# dataloggerver4_1.net
KiCad netlist of a schematic drawn in EAGLE
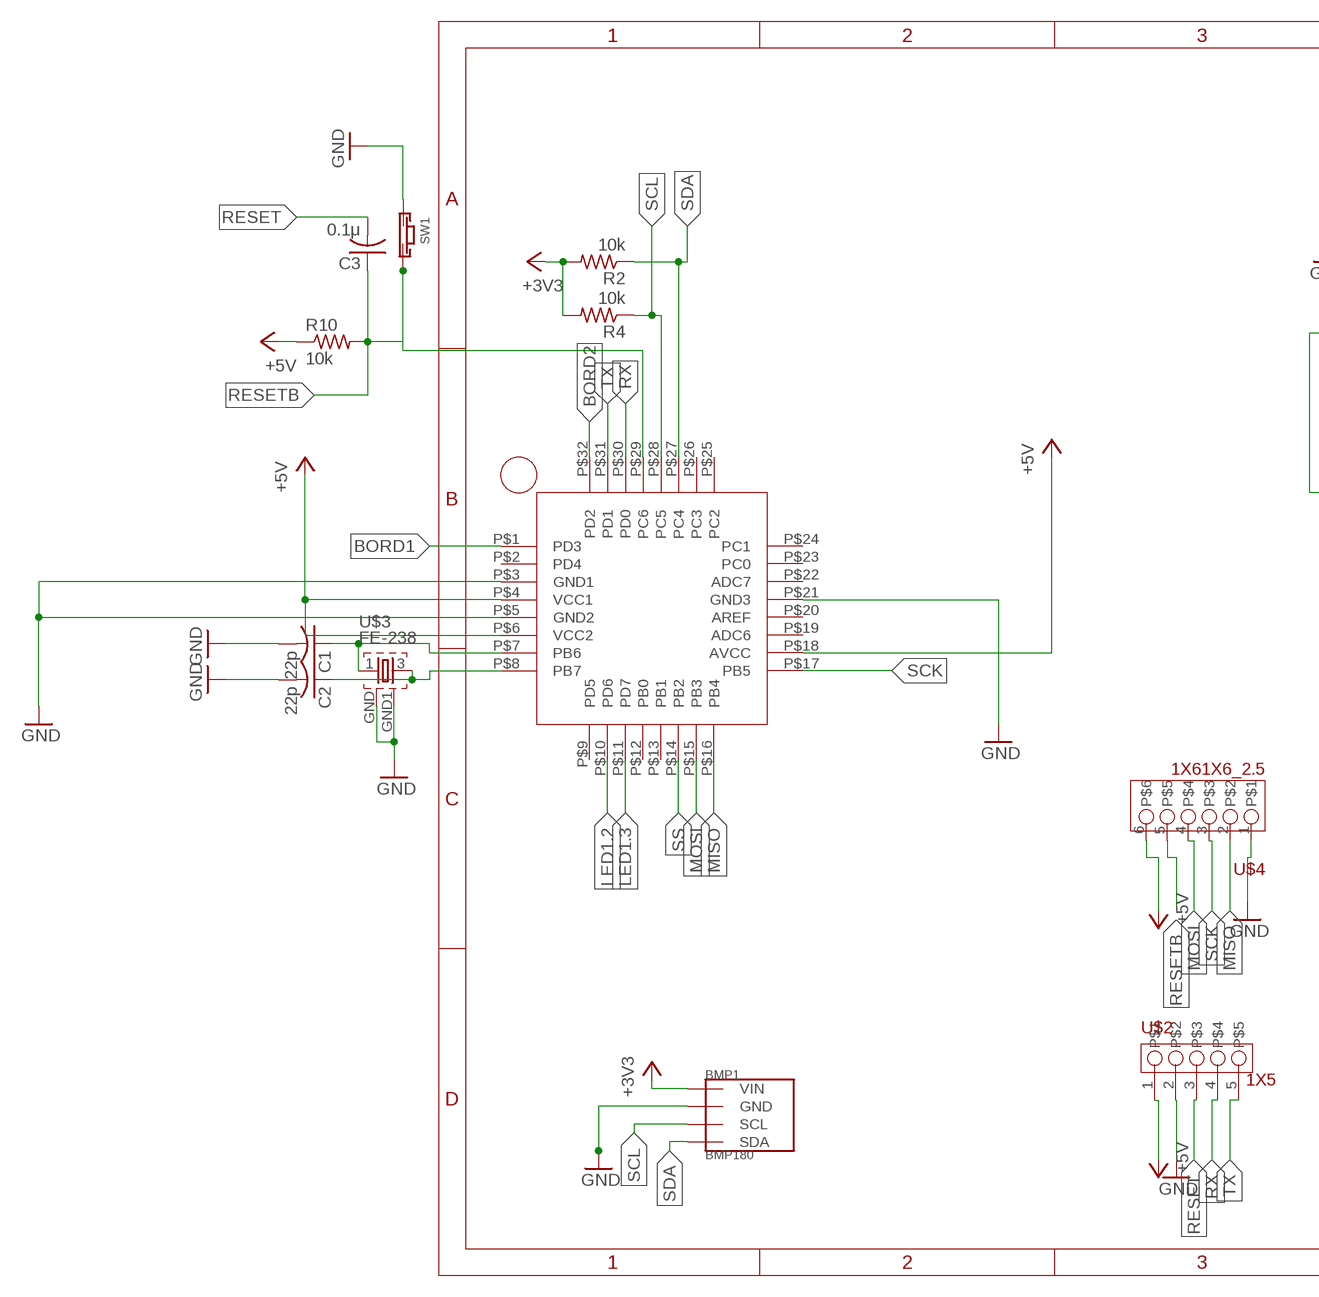
[diagram p0: schematic, sheet 1, part 1 of 2]
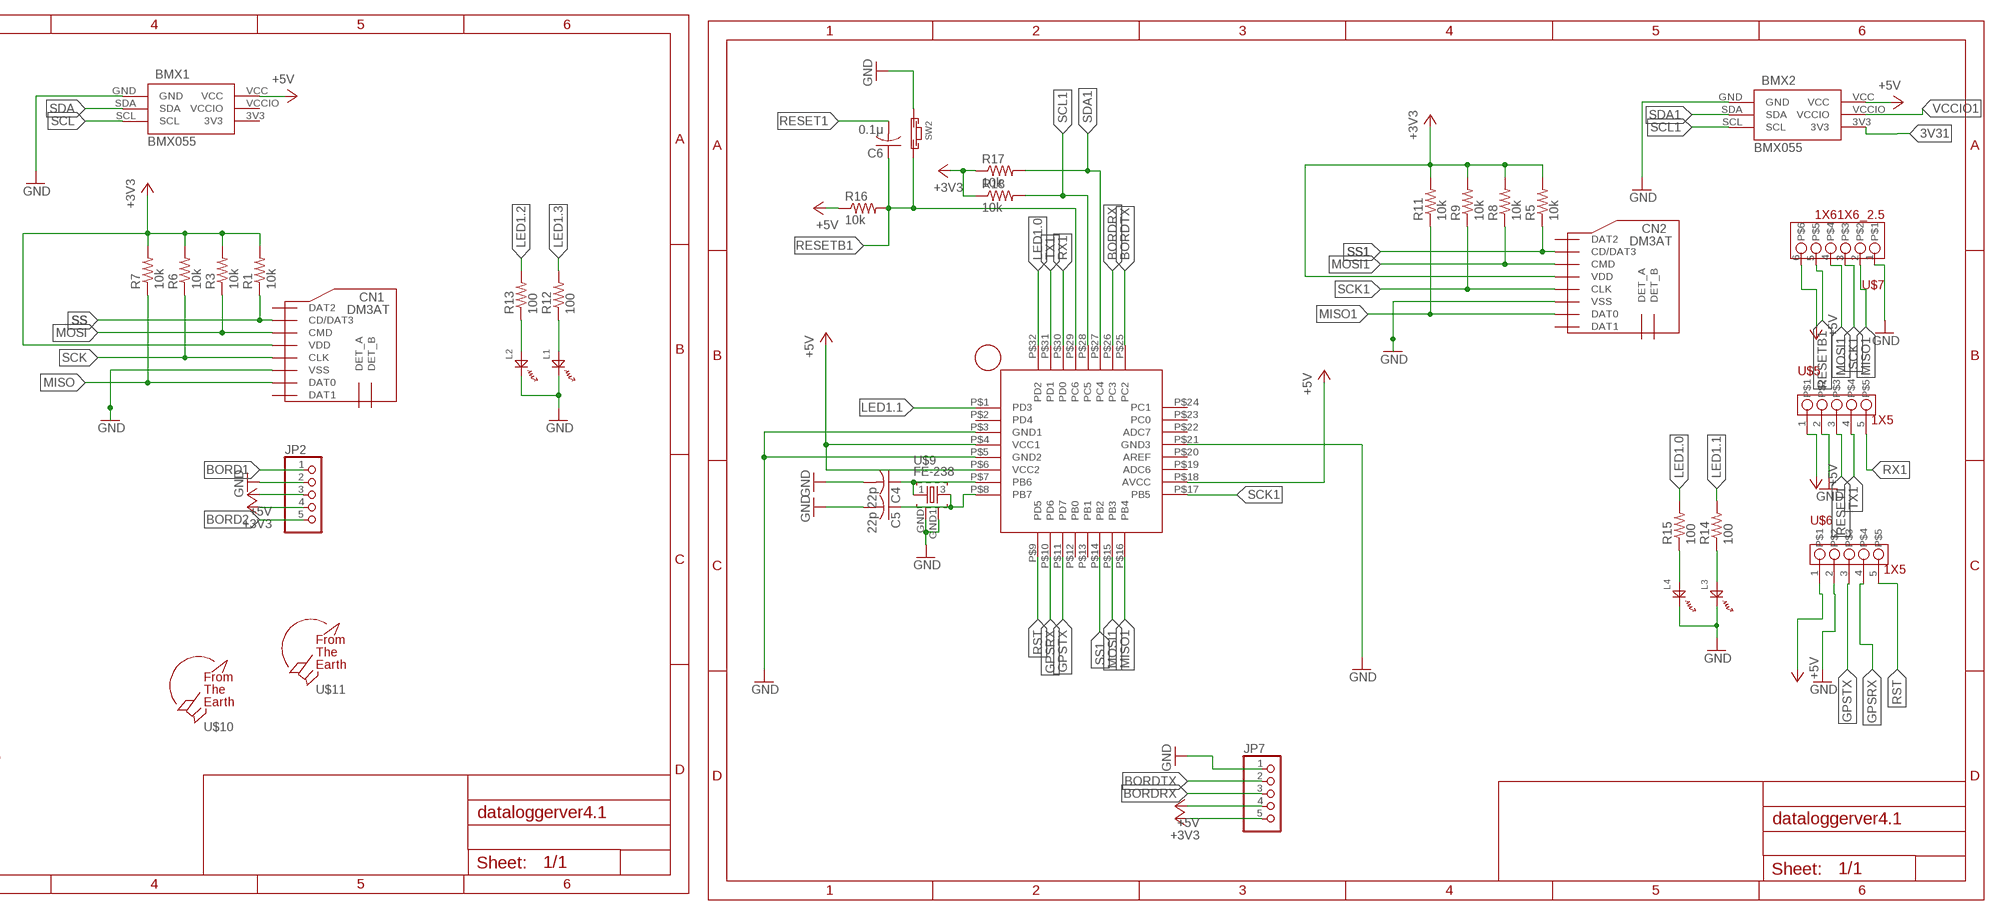
[diagram p1: schematic, sheet 1, part 2 of 2]

(export (version "E")
  (design (tool "Eeschema 10.0.6"))
  (components
    (comp (ref "BMP1")
      (value "BMP180")
      (footprint "eagle-import:GY-68")
      (libsource (lib "eagle-import") (part "BMP180"))
    )
    (comp (ref "BMX1")
      (value "BMX055")
      (footprint "eagle-import:BMX055")
      (libsource (lib "eagle-import") (part "BMX055"))
    )
    (comp (ref "BMX2")
      (value "BMX055")
      (footprint "eagle-import:BMX055")
      (libsource (lib "eagle-import") (part "BMX055"))
    )
    (comp (ref "C1")
      (value "22p")
      (footprint "eagle-import:C1608")
      (libsource (lib "eagle-import") (part "C-USC1608"))
    )
    (comp (ref "C2")
      (value "22p")
      (footprint "eagle-import:C1608")
      (libsource (lib "eagle-import") (part "C-USC1608"))
    )
    (comp (ref "C3")
      (value "0.1μ")
      (footprint "eagle-import:C1608")
      (libsource (lib "eagle-import") (part "C-USC1608"))
    )
    (comp (ref "C4")
      (value "22p")
      (footprint "eagle-import:C1608")
      (libsource (lib "eagle-import") (part "C-USC1608"))
    )
    (comp (ref "C5")
      (value "22p")
      (footprint "eagle-import:C1608")
      (libsource (lib "eagle-import") (part "C-USC1608"))
    )
    (comp (ref "C6")
      (value "0.1μ")
      (footprint "eagle-import:C1608")
      (libsource (lib "eagle-import") (part "C-USC1608"))
    )
    (comp (ref "CN1")
      (value "DM3AT")
      (footprint "eagle-import:DM3AT")
      (libsource (lib "eagle-import") (part "DM3AT"))
    )
    (comp (ref "CN2")
      (value "DM3AT")
      (footprint "eagle-import:DM3AT")
      (libsource (lib "eagle-import") (part "DM3AT"))
    )
    (comp (ref "JP2")
      (value "PINHD-1X5")
      (footprint "eagle-import:1X05")
      (libsource (lib "eagle-import") (part "PINHD-1X5"))
    )
    (comp (ref "JP7")
      (value "PINHD-1X5")
      (footprint "eagle-import:1X05")
      (libsource (lib "eagle-import") (part "PINHD-1X5"))
    )
    (comp (ref "L1")
      (value "OSXX1608C1A")
      (footprint "eagle-import:OSXX1608C1A")
      (libsource (lib "eagle-import") (part "OSXX1608C1A"))
    )
    (comp (ref "L2")
      (value "OSXX1608C1A")
      (footprint "eagle-import:OSXX1608C1A")
      (libsource (lib "eagle-import") (part "OSXX1608C1A"))
    )
    (comp (ref "L3")
      (value "OSXX1608C1A")
      (footprint "eagle-import:OSXX1608C1A")
      (libsource (lib "eagle-import") (part "OSXX1608C1A"))
    )
    (comp (ref "L4")
      (value "OSXX1608C1A")
      (footprint "eagle-import:OSXX1608C1A")
      (libsource (lib "eagle-import") (part "OSXX1608C1A"))
    )
    (comp (ref "R1")
      (value "10k")
      (footprint "eagle-import:R0603")
      (libsource (lib "eagle-import") (part "R-US_R0603"))
    )
    (comp (ref "R2")
      (value "10k")
      (footprint "eagle-import:R0603")
      (libsource (lib "eagle-import") (part "R-US_R0603"))
    )
    (comp (ref "R3")
      (value "10k")
      (footprint "eagle-import:R0603")
      (libsource (lib "eagle-import") (part "R-US_R0603"))
    )
    (comp (ref "R4")
      (value "10k")
      (footprint "eagle-import:R0603")
      (libsource (lib "eagle-import") (part "R-US_R0603"))
    )
    (comp (ref "R5")
      (value "10k")
      (footprint "eagle-import:R0603")
      (libsource (lib "eagle-import") (part "R-US_R0603"))
    )
    (comp (ref "R6")
      (value "10k")
      (footprint "eagle-import:R0603")
      (libsource (lib "eagle-import") (part "R-US_R0603"))
    )
    (comp (ref "R7")
      (value "10k")
      (footprint "eagle-import:R0603")
      (libsource (lib "eagle-import") (part "R-US_R0603"))
    )
    (comp (ref "R8")
      (value "10k")
      (footprint "eagle-import:R0603")
      (libsource (lib "eagle-import") (part "R-US_R0603"))
    )
    (comp (ref "R9")
      (value "10k")
      (footprint "eagle-import:R0603")
      (libsource (lib "eagle-import") (part "R-US_R0603"))
    )
    (comp (ref "R10")
      (value "10k")
      (footprint "eagle-import:R0603")
      (libsource (lib "eagle-import") (part "R-US_R0603"))
    )
    (comp (ref "R11")
      (value "10k")
      (footprint "eagle-import:R0603")
      (libsource (lib "eagle-import") (part "R-US_R0603"))
    )
    (comp (ref "R12")
      (value "100")
      (footprint "eagle-import:R0603")
      (libsource (lib "eagle-import") (part "R-US_R0603"))
    )
    (comp (ref "R13")
      (value "100")
      (footprint "eagle-import:R0603")
      (libsource (lib "eagle-import") (part "R-US_R0603"))
    )
    (comp (ref "R14")
      (value "100")
      (footprint "eagle-import:R0603")
      (libsource (lib "eagle-import") (part "R-US_R0603"))
    )
    (comp (ref "R15")
      (value "100")
      (footprint "eagle-import:R0603")
      (libsource (lib "eagle-import") (part "R-US_R0603"))
    )
    (comp (ref "R16")
      (value "10k")
      (footprint "eagle-import:R0603")
      (libsource (lib "eagle-import") (part "R-US_R0603"))
    )
    (comp (ref "R17")
      (value "10k")
      (footprint "eagle-import:R0603")
      (libsource (lib "eagle-import") (part "R-US_R0603"))
    )
    (comp (ref "R18")
      (value "10k")
      (footprint "eagle-import:R0603")
      (libsource (lib "eagle-import") (part "R-US_R0603"))
    )
    (comp (ref "SW1")
      (value "TVAF06-A020B-R")
      (footprint "eagle-import:TVAF06-A020B-R")
      (libsource (lib "eagle-import") (part "TVAF06-A020B-R"))
    )
    (comp (ref "SW2")
      (value "TVAF06-A020B-R")
      (footprint "eagle-import:TVAF06-A020B-R")
      (libsource (lib "eagle-import") (part "TVAF06-A020B-R"))
    )
    (comp (ref "U$1")
      (value "ATMEGA328P-AUATMEGA328P-AU")
      (footprint "eagle-import:ATMEGA328P-AU")
      (libsource (lib "eagle-import") (part "ATMEGA328P-AUATMEGA328P-AU"))
    )
    (comp (ref "U$2")
      (value "1X5")
      (footprint "eagle-import:HDRVR5W64P254_1X5_1310X250X865B")
      (libsource (lib "eagle-import") (part "1X5"))
    )
    (comp (ref "U$3")
      (value "FE-238")
      (footprint "eagle-import:OSCCC300X230X120N")
      (libsource (lib "eagle-import") (part "FE-238"))
    )
    (comp (ref "U$4")
      (value "1X61X6_2.5")
      (footprint "eagle-import:HDRVR6W64P254_1X6_1564X250X865B")
      (libsource (lib "eagle-import") (part "1X61X6_2.5"))
    )
    (comp (ref "U$5")
      (value "1X5")
      (footprint "eagle-import:HDRVR5W64P254_1X5_1310X250X865B")
      (libsource (lib "eagle-import") (part "1X5"))
    )
    (comp (ref "U$6")
      (value "1X5")
      (footprint "eagle-import:HDRVR5W64P254_1X5_1310X250X865B")
      (libsource (lib "eagle-import") (part "1X5"))
    )
    (comp (ref "U$7")
      (value "1X61X6_2.5")
      (footprint "eagle-import:HDRVR6W64P254_1X6_1564X250X865B")
      (libsource (lib "eagle-import") (part "1X61X6_2.5"))
    )
    (comp (ref "U$8")
      (value "ATMEGA328P-AUATMEGA328P-AU")
      (footprint "eagle-import:ATMEGA328P-AU")
      (libsource (lib "eagle-import") (part "ATMEGA328P-AUATMEGA328P-AU"))
    )
    (comp (ref "U$9")
      (value "FE-238")
      (footprint "eagle-import:OSCCC300X230X120N")
      (libsource (lib "eagle-import") (part "FE-238"))
    )
    (comp (ref "U$10")
      (value "F.T.E.LOGO")
      (footprint "eagle-import:LOGO")
      (libsource (lib "eagle-import") (part "F.T.E.LOGO"))
    )
    (comp (ref "U$11")
      (value "F.T.E.LOGO")
      (footprint "eagle-import:LOGO")
      (libsource (lib "eagle-import") (part "F.T.E.LOGO"))
    )
  )
  (nets
    (net (code "1") (name "+3V3") (class "Default")
      (node (ref "BMP1") (pin "P1") (pinfunction "VIN_P1") (pintype "bidirectional"))
      (node (ref "CN1") (pin "VDD") (pinfunction "VDD_VDD") (pintype "bidirectional"))
      (node (ref "CN2") (pin "VDD") (pinfunction "VDD_VDD") (pintype "bidirectional"))
      (node (ref "JP2") (pin "4") (pinfunction "4_4") (pintype "passive"))
      (node (ref "JP7") (pin "5") (pinfunction "5_5") (pintype "passive"))
      (node (ref "R1") (pin "2") (pinfunction "2_2") (pintype "passive"))
      (node (ref "R11") (pin "2") (pinfunction "2_2") (pintype "passive"))
      (node (ref "R17") (pin "1") (pinfunction "1_1") (pintype "passive"))
      (node (ref "R18") (pin "1") (pinfunction "1_1") (pintype "passive"))
      (node (ref "R2") (pin "2") (pinfunction "2_2") (pintype "passive"))
      (node (ref "R3") (pin "2") (pinfunction "2_2") (pintype "passive"))
      (node (ref "R4") (pin "2") (pinfunction "2_2") (pintype "passive"))
      (node (ref "R5") (pin "2") (pinfunction "2_2") (pintype "passive"))
      (node (ref "R6") (pin "2") (pinfunction "2_2") (pintype "passive"))
      (node (ref "R7") (pin "2") (pinfunction "2_2") (pintype "passive"))
      (node (ref "R8") (pin "2") (pinfunction "2_2") (pintype "passive"))
      (node (ref "R9") (pin "2") (pinfunction "2_2") (pintype "passive"))
    )
    (net (code "2") (name "+5V") (class "Default")
      (node (ref "BMX1") (pin "VCC") (pinfunction "VCC_VCC") (pintype "power_in"))
      (node (ref "BMX2") (pin "VCC") (pinfunction "VCC_VCC") (pintype "power_in"))
      (node (ref "JP2") (pin "3") (pinfunction "3_3") (pintype "passive"))
      (node (ref "JP7") (pin "4") (pinfunction "4_4") (pintype "passive"))
      (node (ref "R10") (pin "1") (pinfunction "1_1") (pintype "passive"))
      (node (ref "R16") (pin "1") (pinfunction "1_1") (pintype "passive"))
      (node (ref "U$1") (pin "P$18") (pinfunction "AVCC_P$18") (pintype "bidirectional"))
      (node (ref "U$1") (pin "P$4") (pinfunction "VCC1_P$4") (pintype "bidirectional"))
      (node (ref "U$1") (pin "P$6") (pinfunction "VCC2_P$6") (pintype "bidirectional"))
      (node (ref "U$2") (pin "1") (pinfunction "P$1_1") (pintype "bidirectional"))
      (node (ref "U$4") (pin "6") (pinfunction "P$6_6") (pintype "bidirectional"))
      (node (ref "U$5") (pin "1") (pinfunction "P$1_1") (pintype "bidirectional"))
      (node (ref "U$6") (pin "1") (pinfunction "P$1_1") (pintype "bidirectional"))
      (node (ref "U$7") (pin "6") (pinfunction "P$6_6") (pintype "bidirectional"))
      (node (ref "U$8") (pin "P$18") (pinfunction "AVCC_P$18") (pintype "bidirectional"))
      (node (ref "U$8") (pin "P$4") (pinfunction "VCC1_P$4") (pintype "bidirectional"))
      (node (ref "U$8") (pin "P$6") (pinfunction "VCC2_P$6") (pintype "bidirectional"))
    )
    (net (code "3") (name "/3V3") (class "Default")
      (node (ref "BMX1") (pin "3V3") (pinfunction "3V3_3V3") (pintype "power_in"))
    )
    (net (code "4") (name "/VCCIO") (class "Default")
      (node (ref "BMX1") (pin "VCCIO") (pinfunction "VCCIO_VCCIO") (pintype "power_in"))
    )
    (net (code "5") (name "3V31") (class "Default")
      (node (ref "BMX2") (pin "3V3") (pinfunction "3V3_3V3") (pintype "power_in"))
    )
    (net (code "6") (name "BORD1") (class "Default")
      (node (ref "JP2") (pin "1") (pinfunction "1_1") (pintype "passive"))
      (node (ref "U$8") (pin "P$1") (pinfunction "PD3_P$1") (pintype "bidirectional"))
    )
    (net (code "7") (name "BORD2") (class "Default")
      (node (ref "JP2") (pin "5") (pinfunction "5_5") (pintype "passive"))
      (node (ref "U$8") (pin "P$32") (pinfunction "PD2_P$32") (pintype "bidirectional"))
    )
    (net (code "8") (name "BORDRX") (class "Default")
      (node (ref "JP7") (pin "3") (pinfunction "3_3") (pintype "passive"))
      (node (ref "U$1") (pin "P$26") (pinfunction "PC3_P$26") (pintype "bidirectional"))
    )
    (net (code "9") (name "BORDTX") (class "Default")
      (node (ref "JP7") (pin "2") (pinfunction "2_2") (pintype "passive"))
      (node (ref "U$1") (pin "P$25") (pinfunction "PC2_P$25") (pintype "bidirectional"))
    )
    (net (code "10") (name "GND") (class "Default")
      (node (ref "BMP1") (pin "P2") (pinfunction "GND_P2") (pintype "bidirectional"))
      (node (ref "BMX1") (pin "GND") (pinfunction "GND_GND") (pintype "power_in"))
      (node (ref "BMX2") (pin "GND") (pinfunction "GND_GND") (pintype "power_in"))
      (node (ref "C1") (pin "2") (pinfunction "2_2") (pintype "passive"))
      (node (ref "C2") (pin "2") (pinfunction "2_2") (pintype "passive"))
      (node (ref "C4") (pin "2") (pinfunction "2_2") (pintype "passive"))
      (node (ref "C5") (pin "2") (pinfunction "2_2") (pintype "passive"))
      (node (ref "CN1") (pin "VSS") (pinfunction "VSS_VSS") (pintype "bidirectional"))
      (node (ref "CN2") (pin "VSS") (pinfunction "VSS_VSS") (pintype "bidirectional"))
      (node (ref "JP2") (pin "2") (pinfunction "2_2") (pintype "passive"))
      (node (ref "JP7") (pin "1") (pinfunction "1_1") (pintype "passive"))
      (node (ref "L1") (pin "CT") (pinfunction "CT_CT") (pintype "bidirectional"))
      (node (ref "L2") (pin "CT") (pinfunction "CT_CT") (pintype "bidirectional"))
      (node (ref "L3") (pin "CT") (pinfunction "CT_CT") (pintype "bidirectional"))
      (node (ref "L4") (pin "CT") (pinfunction "CT_CT") (pintype "bidirectional"))
      (node (ref "SW1") (pin "P$1") (pinfunction "P$1_P$1") (pintype "bidirectional"))
      (node (ref "SW2") (pin "P$1") (pinfunction "P$1_P$1") (pintype "bidirectional"))
      (node (ref "U$1") (pin "P$21") (pinfunction "GND3_P$21") (pintype "bidirectional"))
      (node (ref "U$1") (pin "P$3") (pinfunction "GND1_P$3") (pintype "bidirectional"))
      (node (ref "U$1") (pin "P$5") (pinfunction "GND2_P$5") (pintype "bidirectional"))
      (node (ref "U$2") (pin "2") (pinfunction "P$2_2") (pintype "bidirectional"))
      (node (ref "U$3") (pin "GND") (pinfunction "GND_GND") (pintype "passive"))
      (node (ref "U$3") (pin "GND1") (pinfunction "GND1_GND1") (pintype "passive"))
      (node (ref "U$4") (pin "1") (pinfunction "P$1_1") (pintype "bidirectional"))
      (node (ref "U$5") (pin "2") (pinfunction "P$2_2") (pintype "bidirectional"))
      (node (ref "U$6") (pin "2") (pinfunction "P$2_2") (pintype "bidirectional"))
      (node (ref "U$7") (pin "1") (pinfunction "P$1_1") (pintype "bidirectional"))
      (node (ref "U$8") (pin "P$21") (pinfunction "GND3_P$21") (pintype "bidirectional"))
      (node (ref "U$8") (pin "P$3") (pinfunction "GND1_P$3") (pintype "bidirectional"))
      (node (ref "U$8") (pin "P$5") (pinfunction "GND2_P$5") (pintype "bidirectional"))
      (node (ref "U$9") (pin "GND") (pinfunction "GND_GND") (pintype "passive"))
      (node (ref "U$9") (pin "GND1") (pinfunction "GND1_GND1") (pintype "passive"))
    )
    (net (code "11") (name "GPSRX") (class "Default")
      (node (ref "U$1") (pin "P$10") (pinfunction "PD6_P$10") (pintype "bidirectional"))
      (node (ref "U$6") (pin "4") (pinfunction "P$4_4") (pintype "bidirectional"))
    )
    (net (code "12") (name "GPSTX") (class "Default")
      (node (ref "U$1") (pin "P$11") (pinfunction "PD7_P$11") (pintype "bidirectional"))
      (node (ref "U$6") (pin "3") (pinfunction "P$3_3") (pintype "bidirectional"))
    )
    (net (code "13") (name "LED1.0") (class "Default")
      (node (ref "R15") (pin "2") (pinfunction "2_2") (pintype "passive"))
      (node (ref "U$1") (pin "P$32") (pinfunction "PD2_P$32") (pintype "bidirectional"))
    )
    (net (code "14") (name "LED1.1") (class "Default")
      (node (ref "R14") (pin "2") (pinfunction "2_2") (pintype "passive"))
      (node (ref "U$1") (pin "P$1") (pinfunction "PD3_P$1") (pintype "bidirectional"))
    )
    (net (code "15") (name "LED1.2") (class "Default")
      (node (ref "R13") (pin "2") (pinfunction "2_2") (pintype "passive"))
      (node (ref "U$8") (pin "P$10") (pinfunction "PD6_P$10") (pintype "bidirectional"))
    )
    (net (code "16") (name "LED1.3") (class "Default")
      (node (ref "R12") (pin "2") (pinfunction "2_2") (pintype "passive"))
      (node (ref "U$8") (pin "P$11") (pinfunction "PD7_P$11") (pintype "bidirectional"))
    )
    (net (code "17") (name "MISO") (class "Default")
      (node (ref "CN1") (pin "DAT0") (pinfunction "DAT0_DAT0") (pintype "bidirectional"))
      (node (ref "R7") (pin "1") (pinfunction "1_1") (pintype "passive"))
      (node (ref "U$4") (pin "2") (pinfunction "P$2_2") (pintype "bidirectional"))
      (node (ref "U$8") (pin "P$16") (pinfunction "PB4_P$16") (pintype "bidirectional"))
    )
    (net (code "18") (name "MISO1") (class "Default")
      (node (ref "CN2") (pin "DAT0") (pinfunction "DAT0_DAT0") (pintype "bidirectional"))
      (node (ref "R11") (pin "1") (pinfunction "1_1") (pintype "passive"))
      (node (ref "U$1") (pin "P$16") (pinfunction "PB4_P$16") (pintype "bidirectional"))
      (node (ref "U$7") (pin "2") (pinfunction "P$2_2") (pintype "bidirectional"))
    )
    (net (code "19") (name "MOSI") (class "Default")
      (node (ref "CN1") (pin "CMD") (pinfunction "CMD_CMD") (pintype "bidirectional"))
      (node (ref "R3") (pin "1") (pinfunction "1_1") (pintype "passive"))
      (node (ref "U$4") (pin "4") (pinfunction "P$4_4") (pintype "bidirectional"))
      (node (ref "U$8") (pin "P$15") (pinfunction "PB3_P$15") (pintype "bidirectional"))
    )
    (net (code "20") (name "MOSI1") (class "Default")
      (node (ref "CN2") (pin "CMD") (pinfunction "CMD_CMD") (pintype "bidirectional"))
      (node (ref "R8") (pin "1") (pinfunction "1_1") (pintype "passive"))
      (node (ref "U$1") (pin "P$15") (pinfunction "PB3_P$15") (pintype "bidirectional"))
      (node (ref "U$7") (pin "4") (pinfunction "P$4_4") (pintype "bidirectional"))
    )
    (net (code "21") (name "Net-(L1-PadAN)") (class "Default")
      (node (ref "L1") (pin "AN") (pinfunction "AN_AN") (pintype "bidirectional"))
      (node (ref "R12") (pin "1") (pinfunction "1_1") (pintype "passive"))
    )
    (net (code "22") (name "Net-(L2-PadAN)") (class "Default")
      (node (ref "L2") (pin "AN") (pinfunction "AN_AN") (pintype "bidirectional"))
      (node (ref "R13") (pin "1") (pinfunction "1_1") (pintype "passive"))
    )
    (net (code "23") (name "Net-(L3-PadAN)") (class "Default")
      (node (ref "L3") (pin "AN") (pinfunction "AN_AN") (pintype "bidirectional"))
      (node (ref "R14") (pin "1") (pinfunction "1_1") (pintype "passive"))
    )
    (net (code "24") (name "Net-(L4-PadAN)") (class "Default")
      (node (ref "L4") (pin "AN") (pinfunction "AN_AN") (pintype "bidirectional"))
      (node (ref "R15") (pin "1") (pinfunction "1_1") (pintype "passive"))
    )
    (net (code "25") (name "Net-(U$1-PB6)") (class "Default")
      (node (ref "C4") (pin "1") (pinfunction "1_1") (pintype "passive"))
      (node (ref "U$1") (pin "P$7") (pinfunction "PB6_P$7") (pintype "bidirectional"))
      (node (ref "U$9") (pin "1") (pinfunction "1_1") (pintype "passive"))
    )
    (net (code "26") (name "Net-(U$1-PB7)") (class "Default")
      (node (ref "C5") (pin "1") (pinfunction "1_1") (pintype "passive"))
      (node (ref "U$1") (pin "P$8") (pinfunction "PB7_P$8") (pintype "bidirectional"))
      (node (ref "U$9") (pin "3") (pinfunction "3_3") (pintype "passive"))
    )
    (net (code "27") (name "Net-(U$8-PB6)") (class "Default")
      (node (ref "C1") (pin "1") (pinfunction "1_1") (pintype "passive"))
      (node (ref "U$3") (pin "1") (pinfunction "1_1") (pintype "passive"))
      (node (ref "U$8") (pin "P$7") (pinfunction "PB6_P$7") (pintype "bidirectional"))
    )
    (net (code "28") (name "Net-(U$8-PB7)") (class "Default")
      (node (ref "C2") (pin "1") (pinfunction "1_1") (pintype "passive"))
      (node (ref "U$3") (pin "3") (pinfunction "3_3") (pintype "passive"))
      (node (ref "U$8") (pin "P$8") (pinfunction "PB7_P$8") (pintype "bidirectional"))
    )
    (net (code "29") (name "RESET") (class "Default")
      (node (ref "C3") (pin "2") (pinfunction "2_2") (pintype "passive"))
      (node (ref "U$2") (pin "3") (pinfunction "P$3_3") (pintype "bidirectional"))
    )
    (net (code "30") (name "RESET1") (class "Default")
      (node (ref "C6") (pin "2") (pinfunction "2_2") (pintype "passive"))
      (node (ref "U$5") (pin "3") (pinfunction "P$3_3") (pintype "bidirectional"))
    )
    (net (code "31") (name "RESETB") (class "Default")
      (node (ref "C3") (pin "1") (pinfunction "1_1") (pintype "passive"))
      (node (ref "R10") (pin "2") (pinfunction "2_2") (pintype "passive"))
      (node (ref "SW1") (pin "P$2") (pinfunction "P$2_P$2") (pintype "bidirectional"))
      (node (ref "U$4") (pin "5") (pinfunction "P$5_5") (pintype "bidirectional"))
      (node (ref "U$8") (pin "P$29") (pinfunction "PC6_P$29") (pintype "bidirectional"))
    )
    (net (code "32") (name "RESETB1") (class "Default")
      (node (ref "C6") (pin "1") (pinfunction "1_1") (pintype "passive"))
      (node (ref "R16") (pin "2") (pinfunction "2_2") (pintype "passive"))
      (node (ref "SW2") (pin "P$2") (pinfunction "P$2_P$2") (pintype "bidirectional"))
      (node (ref "U$1") (pin "P$29") (pinfunction "PC6_P$29") (pintype "bidirectional"))
      (node (ref "U$7") (pin "5") (pinfunction "P$5_5") (pintype "bidirectional"))
    )
    (net (code "33") (name "RST") (class "Default")
      (node (ref "U$1") (pin "P$9") (pinfunction "PD5_P$9") (pintype "bidirectional"))
      (node (ref "U$6") (pin "5") (pinfunction "P$5_5") (pintype "bidirectional"))
    )
    (net (code "34") (name "RX") (class "Default")
      (node (ref "U$2") (pin "4") (pinfunction "P$4_4") (pintype "bidirectional"))
      (node (ref "U$8") (pin "P$30") (pinfunction "PD0_P$30") (pintype "bidirectional"))
    )
    (net (code "35") (name "RX1") (class "Default")
      (node (ref "U$1") (pin "P$30") (pinfunction "PD0_P$30") (pintype "bidirectional"))
      (node (ref "U$5") (pin "5") (pinfunction "P$5_5") (pintype "bidirectional"))
    )
    (net (code "36") (name "SCK") (class "Default")
      (node (ref "CN1") (pin "CLK") (pinfunction "CLK_CLK") (pintype "bidirectional"))
      (node (ref "R6") (pin "1") (pinfunction "1_1") (pintype "passive"))
      (node (ref "U$4") (pin "3") (pinfunction "P$3_3") (pintype "bidirectional"))
      (node (ref "U$8") (pin "P$17") (pinfunction "PB5_P$17") (pintype "bidirectional"))
    )
    (net (code "37") (name "SCK1") (class "Default")
      (node (ref "CN2") (pin "CLK") (pinfunction "CLK_CLK") (pintype "bidirectional"))
      (node (ref "R9") (pin "1") (pinfunction "1_1") (pintype "passive"))
      (node (ref "U$1") (pin "P$17") (pinfunction "PB5_P$17") (pintype "bidirectional"))
      (node (ref "U$7") (pin "3") (pinfunction "P$3_3") (pintype "bidirectional"))
    )
    (net (code "38") (name "SCL") (class "Default")
      (node (ref "BMP1") (pin "P3") (pinfunction "SCL_P3") (pintype "bidirectional"))
      (node (ref "BMX1") (pin "SCL") (pinfunction "SCL_SCL") (pintype "bidirectional"))
      (node (ref "R4") (pin "1") (pinfunction "1_1") (pintype "passive"))
      (node (ref "U$8") (pin "P$28") (pinfunction "PC5_P$28") (pintype "bidirectional"))
    )
    (net (code "39") (name "SCL1") (class "Default")
      (node (ref "BMX2") (pin "SCL") (pinfunction "SCL_SCL") (pintype "bidirectional"))
      (node (ref "R18") (pin "2") (pinfunction "2_2") (pintype "passive"))
      (node (ref "U$1") (pin "P$28") (pinfunction "PC5_P$28") (pintype "bidirectional"))
    )
    (net (code "40") (name "SDA") (class "Default")
      (node (ref "BMP1") (pin "P4") (pinfunction "SDA_P4") (pintype "bidirectional"))
      (node (ref "BMX1") (pin "SDA") (pinfunction "SDA_SDA") (pintype "bidirectional"))
      (node (ref "R2") (pin "1") (pinfunction "1_1") (pintype "passive"))
      (node (ref "U$8") (pin "P$27") (pinfunction "PC4_P$27") (pintype "bidirectional"))
    )
    (net (code "41") (name "SDA1") (class "Default")
      (node (ref "BMX2") (pin "SDA") (pinfunction "SDA_SDA") (pintype "bidirectional"))
      (node (ref "R17") (pin "2") (pinfunction "2_2") (pintype "passive"))
      (node (ref "U$1") (pin "P$27") (pinfunction "PC4_P$27") (pintype "bidirectional"))
    )
    (net (code "42") (name "SS") (class "Default")
      (node (ref "CN1") (pin "CD/DAT3") (pinfunction "CD/DAT3_CD/DAT3") (pintype "bidirectional"))
      (node (ref "R1") (pin "1") (pinfunction "1_1") (pintype "passive"))
      (node (ref "U$8") (pin "P$14") (pinfunction "PB2_P$14") (pintype "bidirectional"))
    )
    (net (code "43") (name "SS1") (class "Default")
      (node (ref "CN2") (pin "CD/DAT3") (pinfunction "CD/DAT3_CD/DAT3") (pintype "bidirectional"))
      (node (ref "R5") (pin "1") (pinfunction "1_1") (pintype "passive"))
      (node (ref "U$1") (pin "P$14") (pinfunction "PB2_P$14") (pintype "bidirectional"))
    )
    (net (code "44") (name "TX") (class "Default")
      (node (ref "U$2") (pin "5") (pinfunction "P$5_5") (pintype "bidirectional"))
      (node (ref "U$8") (pin "P$31") (pinfunction "PD1_P$31") (pintype "bidirectional"))
    )
    (net (code "45") (name "TX1") (class "Default")
      (node (ref "U$1") (pin "P$31") (pinfunction "PD1_P$31") (pintype "bidirectional"))
      (node (ref "U$5") (pin "4") (pinfunction "P$4_4") (pintype "bidirectional"))
    )
    (net (code "46") (name "VCCIO1") (class "Default")
      (node (ref "BMX2") (pin "VCCIO") (pinfunction "VCCIO_VCCIO") (pintype "power_in"))
    )
    (net (code "47") (name "unconnected-(CN1-PadDAT1)") (class "Default")
      (node (ref "CN1") (pin "DAT1") (pinfunction "DAT1_DAT1") (pintype "bidirectional"))
    )
    (net (code "48") (name "unconnected-(CN1-PadDAT2)") (class "Default")
      (node (ref "CN1") (pin "DAT2") (pinfunction "DAT2_DAT2") (pintype "bidirectional"))
    )
    (net (code "49") (name "unconnected-(CN1-PadDET_A)") (class "Default")
      (node (ref "CN1") (pin "DET_A") (pinfunction "DET_A_DET_A") (pintype "bidirectional"))
    )
    (net (code "50") (name "unconnected-(CN1-PadDET_B)") (class "Default")
      (node (ref "CN1") (pin "DET_B") (pinfunction "DET_B_DET_B") (pintype "bidirectional"))
    )
    (net (code "51") (name "unconnected-(CN2-PadDAT1)") (class "Default")
      (node (ref "CN2") (pin "DAT1") (pinfunction "DAT1_DAT1") (pintype "bidirectional"))
    )
    (net (code "52") (name "unconnected-(CN2-PadDAT2)") (class "Default")
      (node (ref "CN2") (pin "DAT2") (pinfunction "DAT2_DAT2") (pintype "bidirectional"))
    )
    (net (code "53") (name "unconnected-(CN2-PadDET_A)") (class "Default")
      (node (ref "CN2") (pin "DET_A") (pinfunction "DET_A_DET_A") (pintype "bidirectional"))
    )
    (net (code "54") (name "unconnected-(CN2-PadDET_B)") (class "Default")
      (node (ref "CN2") (pin "DET_B") (pinfunction "DET_B_DET_B") (pintype "bidirectional"))
    )
    (net (code "55") (name "unconnected-(U$1-ADC6-PadP$19)") (class "Default")
      (node (ref "U$1") (pin "P$19") (pinfunction "ADC6_P$19") (pintype "bidirectional"))
    )
    (net (code "56") (name "unconnected-(U$1-ADC7-PadP$22)") (class "Default")
      (node (ref "U$1") (pin "P$22") (pinfunction "ADC7_P$22") (pintype "bidirectional"))
    )
    (net (code "57") (name "unconnected-(U$1-AREF-PadP$20)") (class "Default")
      (node (ref "U$1") (pin "P$20") (pinfunction "AREF_P$20") (pintype "bidirectional"))
    )
    (net (code "58") (name "unconnected-(U$1-PB0-PadP$12)") (class "Default")
      (node (ref "U$1") (pin "P$12") (pinfunction "PB0_P$12") (pintype "bidirectional"))
    )
    (net (code "59") (name "unconnected-(U$1-PB1-PadP$13)") (class "Default")
      (node (ref "U$1") (pin "P$13") (pinfunction "PB1_P$13") (pintype "bidirectional"))
    )
    (net (code "60") (name "unconnected-(U$1-PC0-PadP$23)") (class "Default")
      (node (ref "U$1") (pin "P$23") (pinfunction "PC0_P$23") (pintype "bidirectional"))
    )
    (net (code "61") (name "unconnected-(U$1-PC1-PadP$24)") (class "Default")
      (node (ref "U$1") (pin "P$24") (pinfunction "PC1_P$24") (pintype "bidirectional"))
    )
    (net (code "62") (name "unconnected-(U$1-PD4-PadP$2)") (class "Default")
      (node (ref "U$1") (pin "P$2") (pinfunction "PD4_P$2") (pintype "bidirectional"))
    )
    (net (code "63") (name "unconnected-(U$8-ADC6-PadP$19)") (class "Default")
      (node (ref "U$8") (pin "P$19") (pinfunction "ADC6_P$19") (pintype "bidirectional"))
    )
    (net (code "64") (name "unconnected-(U$8-ADC7-PadP$22)") (class "Default")
      (node (ref "U$8") (pin "P$22") (pinfunction "ADC7_P$22") (pintype "bidirectional"))
    )
    (net (code "65") (name "unconnected-(U$8-AREF-PadP$20)") (class "Default")
      (node (ref "U$8") (pin "P$20") (pinfunction "AREF_P$20") (pintype "bidirectional"))
    )
    (net (code "66") (name "unconnected-(U$8-PB0-PadP$12)") (class "Default")
      (node (ref "U$8") (pin "P$12") (pinfunction "PB0_P$12") (pintype "bidirectional"))
    )
    (net (code "67") (name "unconnected-(U$8-PB1-PadP$13)") (class "Default")
      (node (ref "U$8") (pin "P$13") (pinfunction "PB1_P$13") (pintype "bidirectional"))
    )
    (net (code "68") (name "unconnected-(U$8-PC0-PadP$23)") (class "Default")
      (node (ref "U$8") (pin "P$23") (pinfunction "PC0_P$23") (pintype "bidirectional"))
    )
    (net (code "69") (name "unconnected-(U$8-PC1-PadP$24)") (class "Default")
      (node (ref "U$8") (pin "P$24") (pinfunction "PC1_P$24") (pintype "bidirectional"))
    )
    (net (code "70") (name "unconnected-(U$8-PC2-PadP$25)") (class "Default")
      (node (ref "U$8") (pin "P$25") (pinfunction "PC2_P$25") (pintype "bidirectional"))
    )
    (net (code "71") (name "unconnected-(U$8-PC3-PadP$26)") (class "Default")
      (node (ref "U$8") (pin "P$26") (pinfunction "PC3_P$26") (pintype "bidirectional"))
    )
    (net (code "72") (name "unconnected-(U$8-PD4-PadP$2)") (class "Default")
      (node (ref "U$8") (pin "P$2") (pinfunction "PD4_P$2") (pintype "bidirectional"))
    )
    (net (code "73") (name "unconnected-(U$8-PD5-PadP$9)") (class "Default")
      (node (ref "U$8") (pin "P$9") (pinfunction "PD5_P$9") (pintype "bidirectional"))
    )
  )
)
